# S7G7_footprint_Power_Meter_Only_v1p20.net
KiCad netlist of a schematic drawn in EAGLE
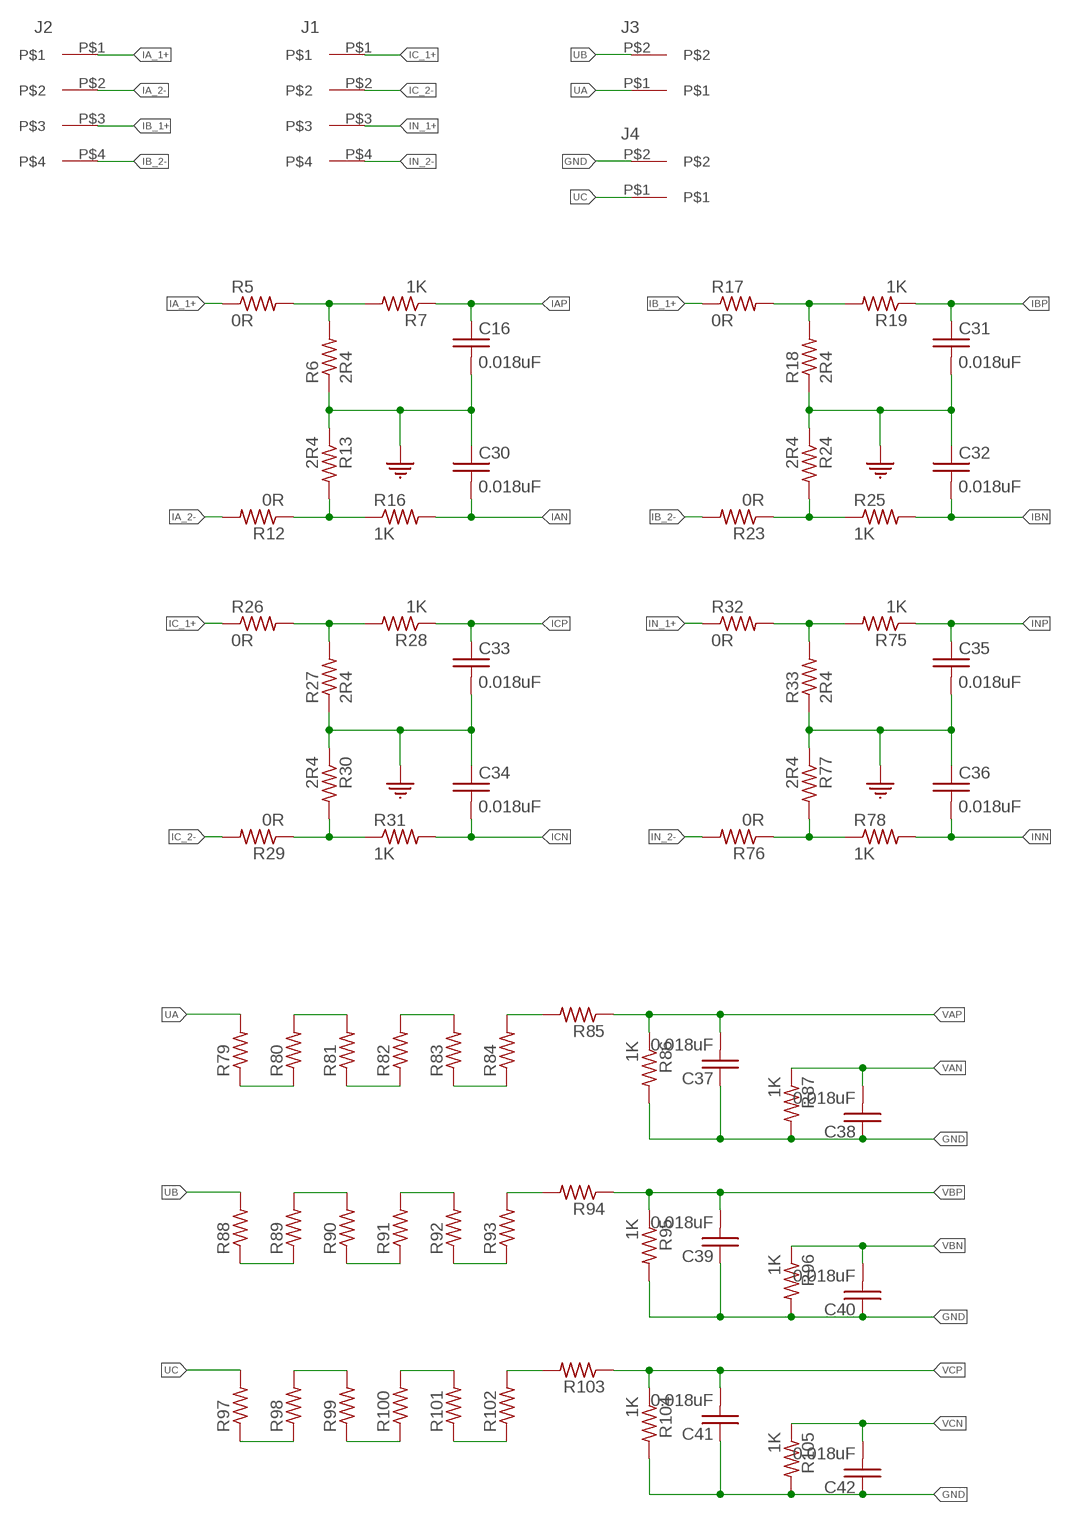
[diagram p0: schematic, sheet 1, part 1 of 2]
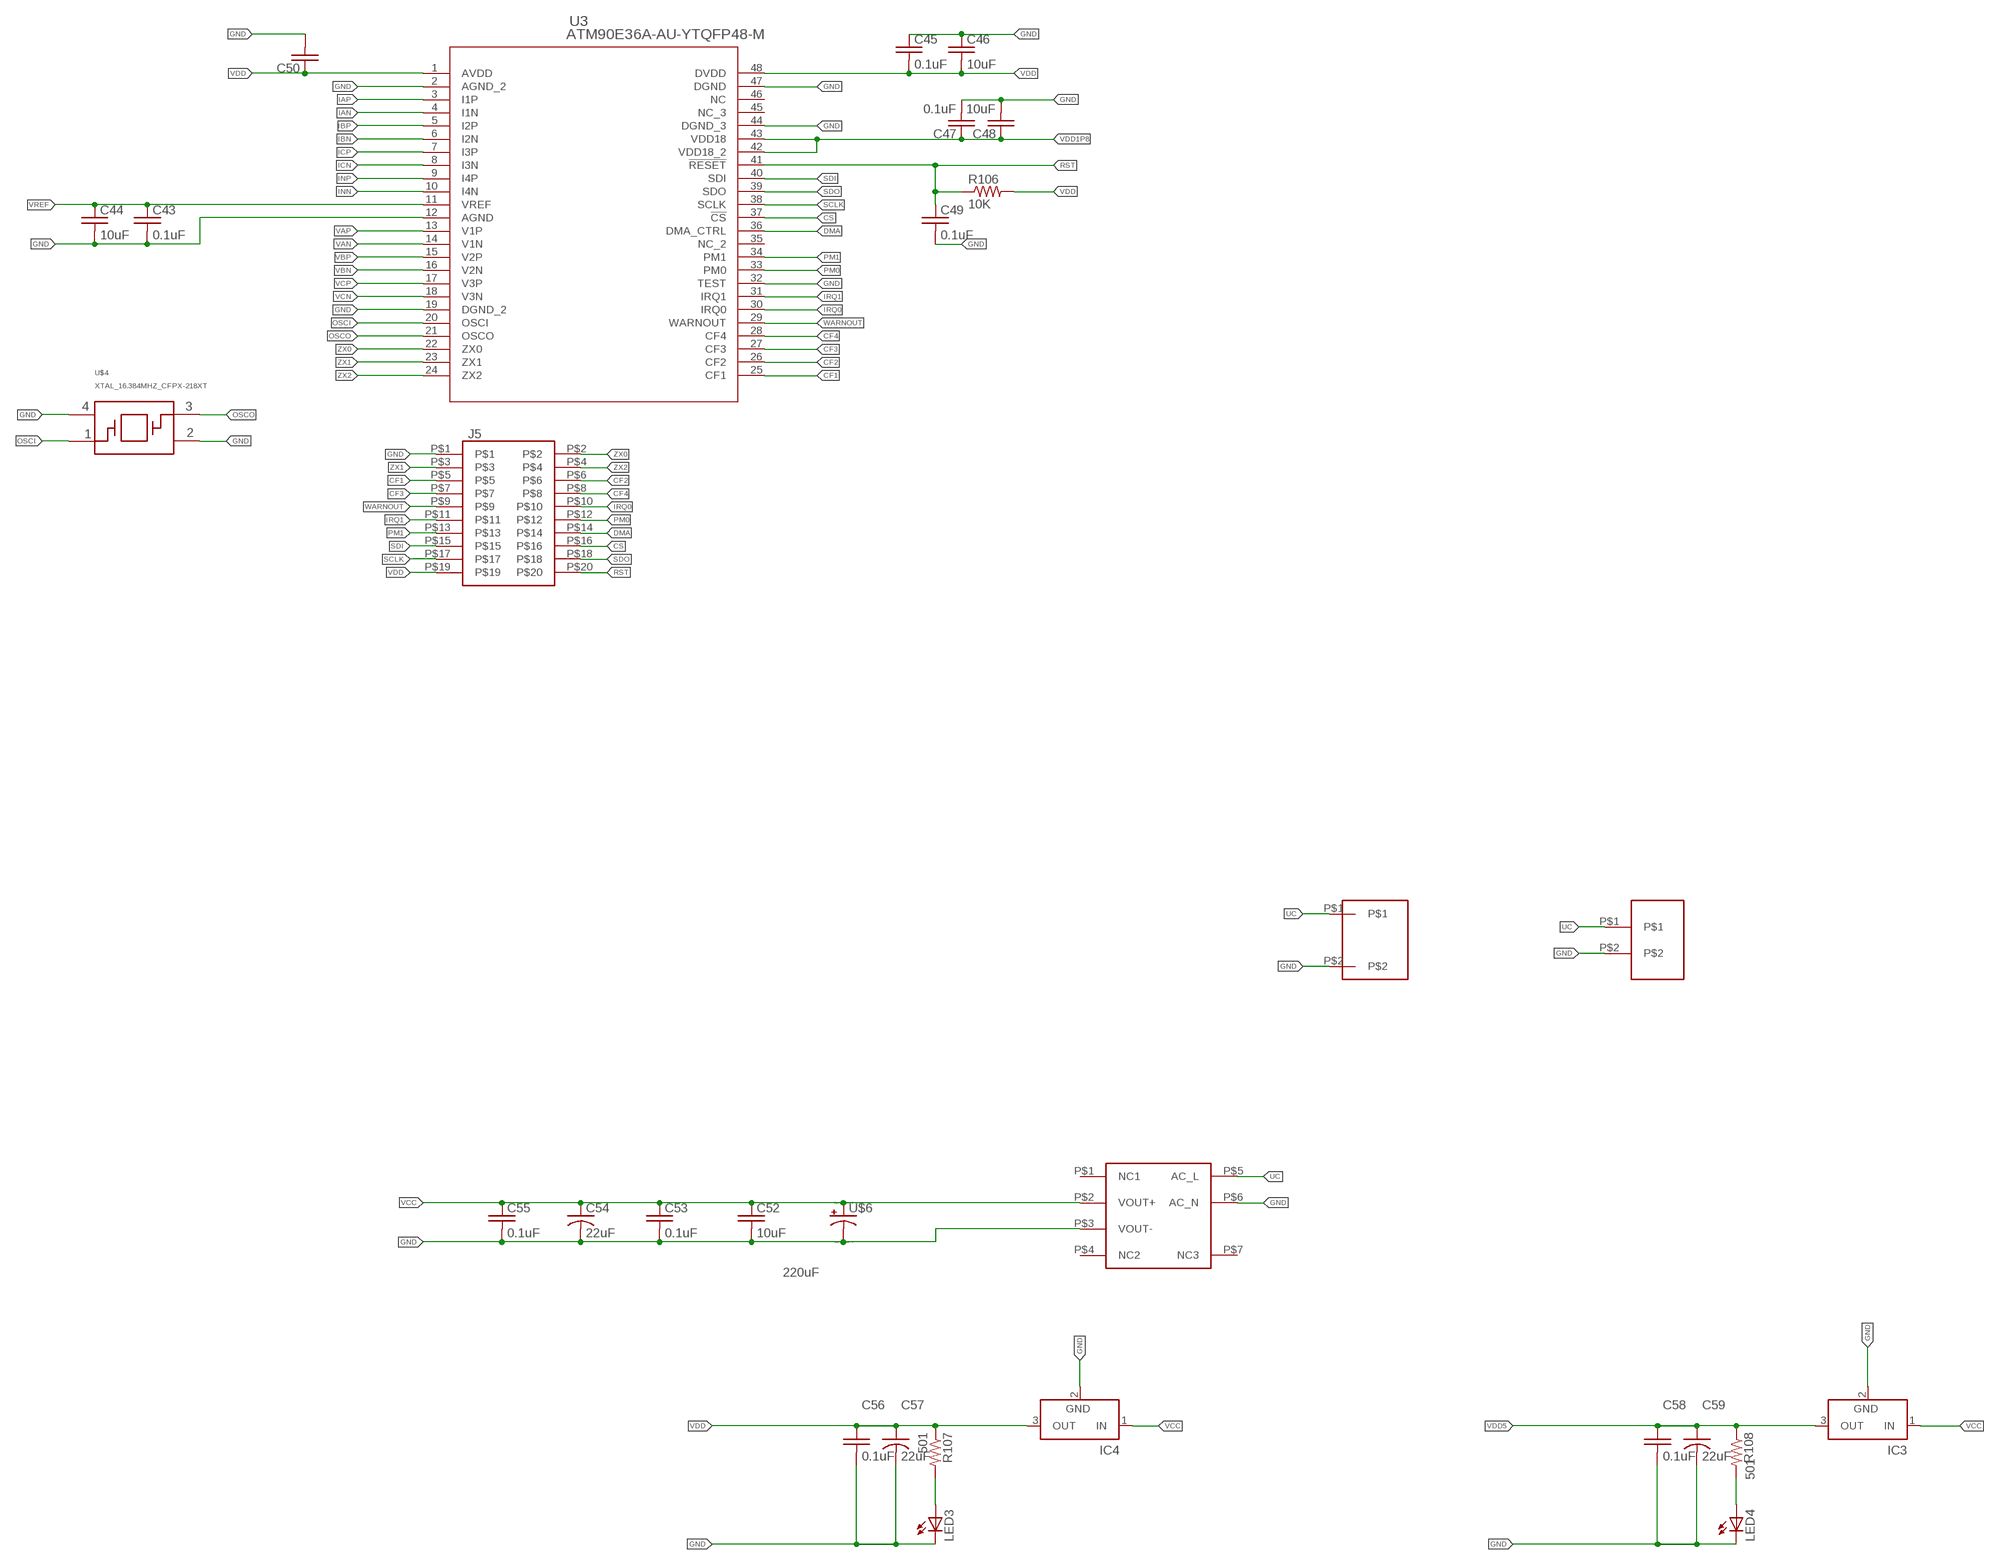
[diagram p1: schematic, sheet 1, part 2 of 2]

(export (version "E")
  (design (tool "Eeschema 10.0.6"))
  (components
    (comp (ref "C16")
      (value "0.018uF")
      (footprint "eagle-import:0402")
      (libsource (lib "eagle-import") (part "C_0402"))
    )
    (comp (ref "C30")
      (value "0.018uF")
      (footprint "eagle-import:0402")
      (libsource (lib "eagle-import") (part "C_0402"))
    )
    (comp (ref "C31")
      (value "0.018uF")
      (footprint "eagle-import:0402")
      (libsource (lib "eagle-import") (part "C_0402"))
    )
    (comp (ref "C32")
      (value "0.018uF")
      (footprint "eagle-import:0402")
      (libsource (lib "eagle-import") (part "C_0402"))
    )
    (comp (ref "C33")
      (value "0.018uF")
      (footprint "eagle-import:0402")
      (libsource (lib "eagle-import") (part "C_0402"))
    )
    (comp (ref "C34")
      (value "0.018uF")
      (footprint "eagle-import:0402")
      (libsource (lib "eagle-import") (part "C_0402"))
    )
    (comp (ref "C35")
      (value "0.018uF")
      (footprint "eagle-import:0402")
      (libsource (lib "eagle-import") (part "C_0402"))
    )
    (comp (ref "C36")
      (value "0.018uF")
      (footprint "eagle-import:0402")
      (libsource (lib "eagle-import") (part "C_0402"))
    )
    (comp (ref "C37")
      (value "0.018uF")
      (footprint "eagle-import:0402")
      (libsource (lib "eagle-import") (part "C_0402"))
    )
    (comp (ref "C38")
      (value "0.018uF")
      (footprint "eagle-import:0402")
      (libsource (lib "eagle-import") (part "C_0402"))
    )
    (comp (ref "C39")
      (value "0.018uF")
      (footprint "eagle-import:0402")
      (libsource (lib "eagle-import") (part "C_0402"))
    )
    (comp (ref "C40")
      (value "0.018uF")
      (footprint "eagle-import:0402")
      (libsource (lib "eagle-import") (part "C_0402"))
    )
    (comp (ref "C41")
      (value "0.018uF")
      (footprint "eagle-import:0402")
      (libsource (lib "eagle-import") (part "C_0402"))
    )
    (comp (ref "C42")
      (value "0.018uF")
      (footprint "eagle-import:0402")
      (libsource (lib "eagle-import") (part "C_0402"))
    )
    (comp (ref "C43")
      (value "0.1uF")
      (footprint "eagle-import:0402")
      (libsource (lib "eagle-import") (part "C_0402"))
    )
    (comp (ref "C44")
      (value "10uF")
      (footprint "eagle-import:0402")
      (libsource (lib "eagle-import") (part "C_0402"))
    )
    (comp (ref "C45")
      (value "0.1uF")
      (footprint "eagle-import:0402")
      (libsource (lib "eagle-import") (part "C_0402"))
    )
    (comp (ref "C46")
      (value "10uF")
      (footprint "eagle-import:0402")
      (libsource (lib "eagle-import") (part "C_0402"))
    )
    (comp (ref "C47")
      (value "0.1uF")
      (footprint "eagle-import:0402")
      (libsource (lib "eagle-import") (part "C_0402"))
    )
    (comp (ref "C48")
      (value "10uF")
      (footprint "eagle-import:0402")
      (libsource (lib "eagle-import") (part "C_0402"))
    )
    (comp (ref "C49")
      (value "0.1uF")
      (footprint "eagle-import:0402")
      (libsource (lib "eagle-import") (part "C_0402"))
    )
    (comp (ref "C50")
      (value "C_0402")
      (footprint "eagle-import:0402")
      (libsource (lib "eagle-import") (part "C_0402"))
    )
    (comp (ref "C51")
      (value "CAP_THIN_FILM_TDK_32922CAP")
      (footprint "eagle-import:CAP_THIN_FILM_32922")
      (libsource (lib "eagle-import") (part "CAP_THIN_FILM_TDK_32922CAP"))
    )
    (comp (ref "C52")
      (value "10uF")
      (footprint "eagle-import:0402")
      (libsource (lib "eagle-import") (part "C_0402"))
    )
    (comp (ref "C53")
      (value "0.1uF")
      (footprint "eagle-import:0402")
      (libsource (lib "eagle-import") (part "C_0402"))
    )
    (comp (ref "C54")
      (value "22uF")
      (footprint "eagle-import:C1206")
      (libsource (lib "eagle-import") (part "C-USC1206"))
    )
    (comp (ref "C55")
      (value "0.1uF")
      (footprint "eagle-import:0402")
      (libsource (lib "eagle-import") (part "C_0402"))
    )
    (comp (ref "C56")
      (value "0.1uF")
      (footprint "eagle-import:0402")
      (libsource (lib "eagle-import") (part "C_0402"))
    )
    (comp (ref "C57")
      (value "22uF")
      (footprint "eagle-import:C1206")
      (libsource (lib "eagle-import") (part "C-USC1206"))
    )
    (comp (ref "C58")
      (value "0.1uF")
      (footprint "eagle-import:0402")
      (libsource (lib "eagle-import") (part "C_0402"))
    )
    (comp (ref "C59")
      (value "22uF")
      (footprint "eagle-import:C1206")
      (libsource (lib "eagle-import") (part "C-USC1206"))
    )
    (comp (ref "IC3")
      (value "LT1129CST5")
      (footprint "eagle-import:SOT223")
      (fields (field (name "MPN") "LT1129CST-5#PBF"))
      (libsource (lib "eagle-import") (part "LT1129CST5"))
    )
    (comp (ref "IC4")
      (value "LT1129CST3")
      (footprint "eagle-import:SOT223")
      (fields (field (name "MPN") "LT1129CST-5#PBF"))
      (libsource (lib "eagle-import") (part "LT1129CST3"))
    )
    (comp (ref "J1")
      (value "3.81MM_1_X_4_RT_ANGLE_PLUG_HEADER")
      (footprint "eagle-import:1X4_3.81MM_PITCH")
      (libsource (lib "eagle-import") (part "3.81MM_1_X_4_RT_ANGLE_PLUG_HEADER"))
    )
    (comp (ref "J2")
      (value "3.81MM_1_X_4_RT_ANGLE_PLUG_HEADER")
      (footprint "eagle-import:1X4_3.81MM_PITCH")
      (libsource (lib "eagle-import") (part "3.81MM_1_X_4_RT_ANGLE_PLUG_HEADER"))
    )
    (comp (ref "J3")
      (value "3.81MM_1_X_2_RT_ANGLE_PLUG_HEADER")
      (footprint "eagle-import:2_3.81MM_PITCH")
      (libsource (lib "eagle-import") (part "3.81MM_1_X_2_RT_ANGLE_PLUG_HEADER"))
    )
    (comp (ref "J4")
      (value "3.81MM_1_X_2_RT_ANGLE_PLUG_HEADER")
      (footprint "eagle-import:2_3.81MM_PITCH")
      (libsource (lib "eagle-import") (part "3.81MM_1_X_2_RT_ANGLE_PLUG_HEADER"))
    )
    (comp (ref "J5")
      (value "2_X_10_HEADER_GENERIC")
      (footprint "eagle-import:2_X_10_.1_INCH")
      (libsource (lib "eagle-import") (part "2_X_10_HEADER_GENERIC"))
    )
    (comp (ref "LED3")
      (value "LED_0805_GREEN")
      (footprint "eagle-import:LED_0805_GREEN")
      (libsource (lib "eagle-import") (part "LED_0805_GREEN"))
    )
    (comp (ref "LED4")
      (value "LED_0805_GREEN")
      (footprint "eagle-import:LED_0805_GREEN")
      (libsource (lib "eagle-import") (part "LED_0805_GREEN"))
    )
    (comp (ref "R5")
      (value "0R")
      (footprint "eagle-import:0402")
      (libsource (lib "eagle-import") (part "R_0402"))
    )
    (comp (ref "R6")
      (value "2R4")
      (footprint "eagle-import:0402")
      (libsource (lib "eagle-import") (part "R_0402"))
    )
    (comp (ref "R7")
      (value "1K")
      (footprint "eagle-import:0402")
      (libsource (lib "eagle-import") (part "R_0402"))
    )
    (comp (ref "R12")
      (value "0R")
      (footprint "eagle-import:0402")
      (libsource (lib "eagle-import") (part "R_0402"))
    )
    (comp (ref "R13")
      (value "2R4")
      (footprint "eagle-import:0402")
      (libsource (lib "eagle-import") (part "R_0402"))
    )
    (comp (ref "R16")
      (value "1K")
      (footprint "eagle-import:0402")
      (libsource (lib "eagle-import") (part "R_0402"))
    )
    (comp (ref "R17")
      (value "0R")
      (footprint "eagle-import:0402")
      (libsource (lib "eagle-import") (part "R_0402"))
    )
    (comp (ref "R18")
      (value "2R4")
      (footprint "eagle-import:0402")
      (libsource (lib "eagle-import") (part "R_0402"))
    )
    (comp (ref "R19")
      (value "1K")
      (footprint "eagle-import:0402")
      (libsource (lib "eagle-import") (part "R_0402"))
    )
    (comp (ref "R23")
      (value "0R")
      (footprint "eagle-import:0402")
      (libsource (lib "eagle-import") (part "R_0402"))
    )
    (comp (ref "R24")
      (value "2R4")
      (footprint "eagle-import:0402")
      (libsource (lib "eagle-import") (part "R_0402"))
    )
    (comp (ref "R25")
      (value "1K")
      (footprint "eagle-import:0402")
      (libsource (lib "eagle-import") (part "R_0402"))
    )
    (comp (ref "R26")
      (value "0R")
      (footprint "eagle-import:0402")
      (libsource (lib "eagle-import") (part "R_0402"))
    )
    (comp (ref "R27")
      (value "2R4")
      (footprint "eagle-import:0402")
      (libsource (lib "eagle-import") (part "R_0402"))
    )
    (comp (ref "R28")
      (value "1K")
      (footprint "eagle-import:0402")
      (libsource (lib "eagle-import") (part "R_0402"))
    )
    (comp (ref "R29")
      (value "0R")
      (footprint "eagle-import:0402")
      (libsource (lib "eagle-import") (part "R_0402"))
    )
    (comp (ref "R30")
      (value "2R4")
      (footprint "eagle-import:0402")
      (libsource (lib "eagle-import") (part "R_0402"))
    )
    (comp (ref "R31")
      (value "1K")
      (footprint "eagle-import:0402")
      (libsource (lib "eagle-import") (part "R_0402"))
    )
    (comp (ref "R32")
      (value "0R")
      (footprint "eagle-import:0402")
      (libsource (lib "eagle-import") (part "R_0402"))
    )
    (comp (ref "R33")
      (value "2R4")
      (footprint "eagle-import:0402")
      (libsource (lib "eagle-import") (part "R_0402"))
    )
    (comp (ref "R75")
      (value "1K")
      (footprint "eagle-import:0402")
      (libsource (lib "eagle-import") (part "R_0402"))
    )
    (comp (ref "R76")
      (value "0R")
      (footprint "eagle-import:0402")
      (libsource (lib "eagle-import") (part "R_0402"))
    )
    (comp (ref "R77")
      (value "2R4")
      (footprint "eagle-import:0402")
      (libsource (lib "eagle-import") (part "R_0402"))
    )
    (comp (ref "R78")
      (value "1K")
      (footprint "eagle-import:0402")
      (libsource (lib "eagle-import") (part "R_0402"))
    )
    (comp (ref "R79")
      (value "R_0402")
      (footprint "eagle-import:0402")
      (libsource (lib "eagle-import") (part "R_0402"))
    )
    (comp (ref "R80")
      (value "R_0402")
      (footprint "eagle-import:0402")
      (libsource (lib "eagle-import") (part "R_0402"))
    )
    (comp (ref "R81")
      (value "R_0402")
      (footprint "eagle-import:0402")
      (libsource (lib "eagle-import") (part "R_0402"))
    )
    (comp (ref "R82")
      (value "R_0402")
      (footprint "eagle-import:0402")
      (libsource (lib "eagle-import") (part "R_0402"))
    )
    (comp (ref "R83")
      (value "R_0402")
      (footprint "eagle-import:0402")
      (libsource (lib "eagle-import") (part "R_0402"))
    )
    (comp (ref "R84")
      (value "R_0402")
      (footprint "eagle-import:0402")
      (libsource (lib "eagle-import") (part "R_0402"))
    )
    (comp (ref "R85")
      (value "R_0402")
      (footprint "eagle-import:0402")
      (libsource (lib "eagle-import") (part "R_0402"))
    )
    (comp (ref "R86")
      (value "1K")
      (footprint "eagle-import:0402")
      (libsource (lib "eagle-import") (part "R_0402"))
    )
    (comp (ref "R87")
      (value "1K")
      (footprint "eagle-import:0402")
      (libsource (lib "eagle-import") (part "R_0402"))
    )
    (comp (ref "R88")
      (value "R_0402")
      (footprint "eagle-import:0402")
      (libsource (lib "eagle-import") (part "R_0402"))
    )
    (comp (ref "R89")
      (value "R_0402")
      (footprint "eagle-import:0402")
      (libsource (lib "eagle-import") (part "R_0402"))
    )
    (comp (ref "R90")
      (value "R_0402")
      (footprint "eagle-import:0402")
      (libsource (lib "eagle-import") (part "R_0402"))
    )
    (comp (ref "R91")
      (value "R_0402")
      (footprint "eagle-import:0402")
      (libsource (lib "eagle-import") (part "R_0402"))
    )
    (comp (ref "R92")
      (value "R_0402")
      (footprint "eagle-import:0402")
      (libsource (lib "eagle-import") (part "R_0402"))
    )
    (comp (ref "R93")
      (value "R_0402")
      (footprint "eagle-import:0402")
      (libsource (lib "eagle-import") (part "R_0402"))
    )
    (comp (ref "R94")
      (value "R_0402")
      (footprint "eagle-import:0402")
      (libsource (lib "eagle-import") (part "R_0402"))
    )
    (comp (ref "R95")
      (value "1K")
      (footprint "eagle-import:0402")
      (libsource (lib "eagle-import") (part "R_0402"))
    )
    (comp (ref "R96")
      (value "1K")
      (footprint "eagle-import:0402")
      (libsource (lib "eagle-import") (part "R_0402"))
    )
    (comp (ref "R97")
      (value "R_0402")
      (footprint "eagle-import:0402")
      (libsource (lib "eagle-import") (part "R_0402"))
    )
    (comp (ref "R98")
      (value "R_0402")
      (footprint "eagle-import:0402")
      (libsource (lib "eagle-import") (part "R_0402"))
    )
    (comp (ref "R99")
      (value "R_0402")
      (footprint "eagle-import:0402")
      (libsource (lib "eagle-import") (part "R_0402"))
    )
    (comp (ref "R100")
      (value "R_0402")
      (footprint "eagle-import:0402")
      (libsource (lib "eagle-import") (part "R_0402"))
    )
    (comp (ref "R101")
      (value "R_0402")
      (footprint "eagle-import:0402")
      (libsource (lib "eagle-import") (part "R_0402"))
    )
    (comp (ref "R102")
      (value "R_0402")
      (footprint "eagle-import:0402")
      (libsource (lib "eagle-import") (part "R_0402"))
    )
    (comp (ref "R103")
      (value "R_0402")
      (footprint "eagle-import:0402")
      (libsource (lib "eagle-import") (part "R_0402"))
    )
    (comp (ref "R104")
      (value "1K")
      (footprint "eagle-import:0402")
      (libsource (lib "eagle-import") (part "R_0402"))
    )
    (comp (ref "R105")
      (value "1K")
      (footprint "eagle-import:0402")
      (libsource (lib "eagle-import") (part "R_0402"))
    )
    (comp (ref "R106")
      (value "10K")
      (footprint "eagle-import:0402")
      (libsource (lib "eagle-import") (part "R_0402"))
    )
    (comp (ref "R107")
      (value "501")
      (footprint "eagle-import:0402")
      (libsource (lib "eagle-import") (part "R_0402"))
    )
    (comp (ref "R108")
      (value "501")
      (footprint "eagle-import:0402")
      (libsource (lib "eagle-import") (part "R_0402"))
    )
    (comp (ref "U$4")
      (value "XTAL_16.384MHZ_CFPX-218XT")
      (footprint "eagle-import:XTAL_2.5X2.0")
      (libsource (lib "eagle-import") (part "XTAL_16.384MHZ_CFPX-218XT"))
    )
    (comp (ref "U$5")
      (value "VAR_10MM_VDRUS10")
      (footprint "eagle-import:VAR_10MM_VDRUS10")
      (libsource (lib "eagle-import") (part "VAR_10MM_VDRUS10"))
    )
    (comp (ref "U$6")
      (value "220uF")
      (footprint "eagle-import:C_AL_ELECTROLYTIC_SMD_220UF")
      (libsource (lib "eagle-import") (part "C_AL_ELECTROLYTIC_SMD_220UF"))
    )
    (comp (ref "U3")
      (value "ATM90E36A-AU-YTQFP48-M")
      (footprint "eagle-import:TQFP48-M")
      (fields (field (name "MANUFACTURER_PART_NUMBER") "ATM90E36AAUY"))
      (libsource (lib "eagle-import") (part "ATM90E36A-AU-YTQFP48-M"))
    )
    (comp (ref "U4")
      (value "TMLM_04109")
      (footprint "eagle-import:TMLM04")
      (libsource (lib "eagle-import") (part "TMLM_04109"))
    )
  )
  (nets
    (net (code "1") (name "CF1") (class "Default")
      (node (ref "J5") (pin "P$5") (pinfunction "P$5_P$5") (pintype "bidirectional"))
      (node (ref "U3") (pin "25") (pinfunction "CF1_25") (pintype "output"))
    )
    (net (code "2") (name "CF2") (class "Default")
      (node (ref "J5") (pin "P$6") (pinfunction "P$6_P$6") (pintype "bidirectional"))
      (node (ref "U3") (pin "26") (pinfunction "CF2_26") (pintype "output"))
    )
    (net (code "3") (name "CF3") (class "Default")
      (node (ref "J5") (pin "P$7") (pinfunction "P$7_P$7") (pintype "bidirectional"))
      (node (ref "U3") (pin "27") (pinfunction "CF3_27") (pintype "output"))
    )
    (net (code "4") (name "CF4") (class "Default")
      (node (ref "J5") (pin "P$8") (pinfunction "P$8_P$8") (pintype "bidirectional"))
      (node (ref "U3") (pin "28") (pinfunction "CF4_28") (pintype "output"))
    )
    (net (code "5") (name "CS") (class "Default")
      (node (ref "J5") (pin "P$16") (pinfunction "P$16_P$16") (pintype "bidirectional"))
      (node (ref "U3") (pin "37") (pinfunction "~{CS}_37") (pintype "bidirectional"))
    )
    (net (code "6") (name "DMA") (class "Default")
      (node (ref "J5") (pin "P$14") (pinfunction "P$14_P$14") (pintype "bidirectional"))
      (node (ref "U3") (pin "36") (pinfunction "DMA_CTRL_36") (pintype "input"))
    )
    (net (code "7") (name "GND") (class "Default")
      (node (ref "C16") (pin "P$2") (pinfunction "2_P$2") (pintype "passive"))
      (node (ref "C30") (pin "P$1") (pinfunction "1_P$1") (pintype "passive"))
      (node (ref "C31") (pin "P$2") (pinfunction "2_P$2") (pintype "passive"))
      (node (ref "C32") (pin "P$1") (pinfunction "1_P$1") (pintype "passive"))
      (node (ref "C33") (pin "P$2") (pinfunction "2_P$2") (pintype "passive"))
      (node (ref "C34") (pin "P$1") (pinfunction "1_P$1") (pintype "passive"))
      (node (ref "C35") (pin "P$2") (pinfunction "2_P$2") (pintype "passive"))
      (node (ref "C36") (pin "P$1") (pinfunction "1_P$1") (pintype "passive"))
      (node (ref "C37") (pin "P$1") (pinfunction "1_P$1") (pintype "passive"))
      (node (ref "C38") (pin "P$1") (pinfunction "1_P$1") (pintype "passive"))
      (node (ref "C39") (pin "P$1") (pinfunction "1_P$1") (pintype "passive"))
      (node (ref "C40") (pin "P$1") (pinfunction "1_P$1") (pintype "passive"))
      (node (ref "C41") (pin "P$1") (pinfunction "1_P$1") (pintype "passive"))
      (node (ref "C42") (pin "P$1") (pinfunction "1_P$1") (pintype "passive"))
      (node (ref "C43") (pin "P$2") (pinfunction "2_P$2") (pintype "passive"))
      (node (ref "C44") (pin "P$2") (pinfunction "2_P$2") (pintype "passive"))
      (node (ref "C45") (pin "P$1") (pinfunction "1_P$1") (pintype "passive"))
      (node (ref "C46") (pin "P$1") (pinfunction "1_P$1") (pintype "passive"))
      (node (ref "C47") (pin "P$2") (pinfunction "2_P$2") (pintype "passive"))
      (node (ref "C48") (pin "P$2") (pinfunction "2_P$2") (pintype "passive"))
      (node (ref "C49") (pin "P$2") (pinfunction "2_P$2") (pintype "passive"))
      (node (ref "C50") (pin "P$2") (pinfunction "2_P$2") (pintype "passive"))
      (node (ref "C51") (pin "P$2") (pinfunction "P$2_P$2") (pintype "bidirectional"))
      (node (ref "C52") (pin "P$2") (pinfunction "2_P$2") (pintype "passive"))
      (node (ref "C53") (pin "P$2") (pinfunction "2_P$2") (pintype "passive"))
      (node (ref "C54") (pin "2") (pinfunction "2_2") (pintype "passive"))
      (node (ref "C55") (pin "P$2") (pinfunction "2_P$2") (pintype "passive"))
      (node (ref "C56") (pin "P$2") (pinfunction "2_P$2") (pintype "passive"))
      (node (ref "C57") (pin "2") (pinfunction "2_2") (pintype "passive"))
      (node (ref "C58") (pin "P$2") (pinfunction "2_P$2") (pintype "passive"))
      (node (ref "C59") (pin "2") (pinfunction "2_2") (pintype "passive"))
      (node (ref "IC3") (pin "2") (pinfunction "GND_2") (pintype "power_in"))
      (node (ref "IC4") (pin "2") (pinfunction "GND_2") (pintype "power_in"))
      (node (ref "J4") (pin "P$2") (pinfunction "P$2_P$2") (pintype "bidirectional"))
      (node (ref "J5") (pin "P$1") (pinfunction "P$1_P$1") (pintype "bidirectional"))
      (node (ref "LED3") (pin "C") (pinfunction "C_C") (pintype "passive"))
      (node (ref "LED4") (pin "C") (pinfunction "C_C") (pintype "passive"))
      (node (ref "R104") (pin "P$2") (pinfunction "2_P$2") (pintype "passive"))
      (node (ref "R105") (pin "P$2") (pinfunction "2_P$2") (pintype "passive"))
      (node (ref "R13") (pin "P$1") (pinfunction "1_P$1") (pintype "passive"))
      (node (ref "R18") (pin "P$1") (pinfunction "1_P$1") (pintype "passive"))
      (node (ref "R24") (pin "P$1") (pinfunction "1_P$1") (pintype "passive"))
      (node (ref "R27") (pin "P$1") (pinfunction "1_P$1") (pintype "passive"))
      (node (ref "R30") (pin "P$1") (pinfunction "1_P$1") (pintype "passive"))
      (node (ref "R33") (pin "P$1") (pinfunction "1_P$1") (pintype "passive"))
      (node (ref "R6") (pin "P$1") (pinfunction "1_P$1") (pintype "passive"))
      (node (ref "R77") (pin "P$1") (pinfunction "1_P$1") (pintype "passive"))
      (node (ref "R86") (pin "P$2") (pinfunction "2_P$2") (pintype "passive"))
      (node (ref "R87") (pin "P$2") (pinfunction "2_P$2") (pintype "passive"))
      (node (ref "R95") (pin "P$2") (pinfunction "2_P$2") (pintype "passive"))
      (node (ref "R96") (pin "P$2") (pinfunction "2_P$2") (pintype "passive"))
      (node (ref "U$4") (pin "2") (pinfunction "2_2") (pintype "bidirectional"))
      (node (ref "U$4") (pin "4") (pinfunction "4_4") (pintype "bidirectional"))
      (node (ref "U$5") (pin "P$2") (pinfunction "P$2_P$2") (pintype "bidirectional"))
      (node (ref "U$6") (pin "N-") (pinfunction "-_N-") (pintype "passive"))
      (node (ref "U3") (pin "12") (pinfunction "AGND_12") (pintype "power_in"))
      (node (ref "U3") (pin "19") (pinfunction "DGND_2_19") (pintype "power_in"))
      (node (ref "U3") (pin "2") (pinfunction "AGND_2_2") (pintype "power_in"))
      (node (ref "U3") (pin "32") (pinfunction "TEST_32") (pintype "input"))
      (node (ref "U3") (pin "44") (pinfunction "DGND_3_44") (pintype "power_in"))
      (node (ref "U3") (pin "47") (pinfunction "DGND_47") (pintype "power_in"))
      (node (ref "U4") (pin "P$3") (pinfunction "VOUT-_P$3") (pintype "bidirectional"))
      (node (ref "U4") (pin "P$6") (pinfunction "AC_N_P$6") (pintype "bidirectional"))
    )
    (net (code "8") (name "IAN") (class "Default")
      (node (ref "C30") (pin "P$2") (pinfunction "2_P$2") (pintype "passive"))
      (node (ref "R16") (pin "P$2") (pinfunction "2_P$2") (pintype "passive"))
      (node (ref "U3") (pin "4") (pinfunction "I1N_4") (pintype "input"))
    )
    (net (code "9") (name "IAP") (class "Default")
      (node (ref "C16") (pin "P$1") (pinfunction "1_P$1") (pintype "passive"))
      (node (ref "R7") (pin "P$1") (pinfunction "1_P$1") (pintype "passive"))
      (node (ref "U3") (pin "3") (pinfunction "I1P_3") (pintype "input"))
    )
    (net (code "10") (name "IA_1+") (class "Default")
      (node (ref "J2") (pin "P$1") (pinfunction "P$1_P$1") (pintype "bidirectional"))
      (node (ref "R5") (pin "P$1") (pinfunction "1_P$1") (pintype "passive"))
    )
    (net (code "11") (name "IA_2-") (class "Default")
      (node (ref "J2") (pin "P$2") (pinfunction "P$2_P$2") (pintype "bidirectional"))
      (node (ref "R12") (pin "P$2") (pinfunction "2_P$2") (pintype "passive"))
    )
    (net (code "12") (name "IBN") (class "Default")
      (node (ref "C32") (pin "P$2") (pinfunction "2_P$2") (pintype "passive"))
      (node (ref "R25") (pin "P$2") (pinfunction "2_P$2") (pintype "passive"))
      (node (ref "U3") (pin "6") (pinfunction "I2N_6") (pintype "input"))
    )
    (net (code "13") (name "IBP") (class "Default")
      (node (ref "C31") (pin "P$1") (pinfunction "1_P$1") (pintype "passive"))
      (node (ref "R19") (pin "P$1") (pinfunction "1_P$1") (pintype "passive"))
      (node (ref "U3") (pin "5") (pinfunction "I2P_5") (pintype "input"))
    )
    (net (code "14") (name "IB_1+") (class "Default")
      (node (ref "J2") (pin "P$3") (pinfunction "P$3_P$3") (pintype "bidirectional"))
      (node (ref "R17") (pin "P$1") (pinfunction "1_P$1") (pintype "passive"))
    )
    (net (code "15") (name "IB_2-") (class "Default")
      (node (ref "J2") (pin "P$4") (pinfunction "P$4_P$4") (pintype "bidirectional"))
      (node (ref "R23") (pin "P$2") (pinfunction "2_P$2") (pintype "passive"))
    )
    (net (code "16") (name "ICN") (class "Default")
      (node (ref "C34") (pin "P$2") (pinfunction "2_P$2") (pintype "passive"))
      (node (ref "R31") (pin "P$2") (pinfunction "2_P$2") (pintype "passive"))
      (node (ref "U3") (pin "8") (pinfunction "I3N_8") (pintype "input"))
    )
    (net (code "17") (name "ICP") (class "Default")
      (node (ref "C33") (pin "P$1") (pinfunction "1_P$1") (pintype "passive"))
      (node (ref "R28") (pin "P$1") (pinfunction "1_P$1") (pintype "passive"))
      (node (ref "U3") (pin "7") (pinfunction "I3P_7") (pintype "input"))
    )
    (net (code "18") (name "IC_1+") (class "Default")
      (node (ref "J1") (pin "P$1") (pinfunction "P$1_P$1") (pintype "bidirectional"))
      (node (ref "R26") (pin "P$1") (pinfunction "1_P$1") (pintype "passive"))
    )
    (net (code "19") (name "IC_2-") (class "Default")
      (node (ref "J1") (pin "P$2") (pinfunction "P$2_P$2") (pintype "bidirectional"))
      (node (ref "R29") (pin "P$2") (pinfunction "2_P$2") (pintype "passive"))
    )
    (net (code "20") (name "INN") (class "Default")
      (node (ref "C36") (pin "P$2") (pinfunction "2_P$2") (pintype "passive"))
      (node (ref "R78") (pin "P$2") (pinfunction "2_P$2") (pintype "passive"))
      (node (ref "U3") (pin "10") (pinfunction "I4N_10") (pintype "input"))
    )
    (net (code "21") (name "INP") (class "Default")
      (node (ref "C35") (pin "P$1") (pinfunction "1_P$1") (pintype "passive"))
      (node (ref "R75") (pin "P$1") (pinfunction "1_P$1") (pintype "passive"))
      (node (ref "U3") (pin "9") (pinfunction "I4P_9") (pintype "input"))
    )
    (net (code "22") (name "IN_1+") (class "Default")
      (node (ref "J1") (pin "P$3") (pinfunction "P$3_P$3") (pintype "bidirectional"))
      (node (ref "R32") (pin "P$1") (pinfunction "1_P$1") (pintype "passive"))
    )
    (net (code "23") (name "IN_2-") (class "Default")
      (node (ref "J1") (pin "P$4") (pinfunction "P$4_P$4") (pintype "bidirectional"))
      (node (ref "R76") (pin "P$2") (pinfunction "2_P$2") (pintype "passive"))
    )
    (net (code "24") (name "IRQ0") (class "Default")
      (node (ref "J5") (pin "P$10") (pinfunction "P$10_P$10") (pintype "bidirectional"))
      (node (ref "U3") (pin "30") (pinfunction "IRQ0_30") (pintype "output"))
    )
    (net (code "25") (name "IRQ1") (class "Default")
      (node (ref "J5") (pin "P$11") (pinfunction "P$11_P$11") (pintype "bidirectional"))
      (node (ref "U3") (pin "31") (pinfunction "IRQ1_31") (pintype "output"))
    )
    (net (code "26") (name "Net-(R5-2)") (class "Default")
      (node (ref "R5") (pin "P$2") (pinfunction "2_P$2") (pintype "passive"))
      (node (ref "R6") (pin "P$2") (pinfunction "2_P$2") (pintype "passive"))
      (node (ref "R7") (pin "P$2") (pinfunction "2_P$2") (pintype "passive"))
    )
    (net (code "27") (name "Net-(R12-1)") (class "Default")
      (node (ref "R12") (pin "P$1") (pinfunction "1_P$1") (pintype "passive"))
      (node (ref "R13") (pin "P$2") (pinfunction "2_P$2") (pintype "passive"))
      (node (ref "R16") (pin "P$1") (pinfunction "1_P$1") (pintype "passive"))
    )
    (net (code "28") (name "Net-(R17-2)") (class "Default")
      (node (ref "R17") (pin "P$2") (pinfunction "2_P$2") (pintype "passive"))
      (node (ref "R18") (pin "P$2") (pinfunction "2_P$2") (pintype "passive"))
      (node (ref "R19") (pin "P$2") (pinfunction "2_P$2") (pintype "passive"))
    )
    (net (code "29") (name "Net-(R23-1)") (class "Default")
      (node (ref "R23") (pin "P$1") (pinfunction "1_P$1") (pintype "passive"))
      (node (ref "R24") (pin "P$2") (pinfunction "2_P$2") (pintype "passive"))
      (node (ref "R25") (pin "P$1") (pinfunction "1_P$1") (pintype "passive"))
    )
    (net (code "30") (name "Net-(R26-2)") (class "Default")
      (node (ref "R26") (pin "P$2") (pinfunction "2_P$2") (pintype "passive"))
      (node (ref "R27") (pin "P$2") (pinfunction "2_P$2") (pintype "passive"))
      (node (ref "R28") (pin "P$2") (pinfunction "2_P$2") (pintype "passive"))
    )
    (net (code "31") (name "Net-(R29-1)") (class "Default")
      (node (ref "R29") (pin "P$1") (pinfunction "1_P$1") (pintype "passive"))
      (node (ref "R30") (pin "P$2") (pinfunction "2_P$2") (pintype "passive"))
      (node (ref "R31") (pin "P$1") (pinfunction "1_P$1") (pintype "passive"))
    )
    (net (code "32") (name "Net-(R32-2)") (class "Default")
      (node (ref "R32") (pin "P$2") (pinfunction "2_P$2") (pintype "passive"))
      (node (ref "R33") (pin "P$2") (pinfunction "2_P$2") (pintype "passive"))
      (node (ref "R75") (pin "P$2") (pinfunction "2_P$2") (pintype "passive"))
    )
    (net (code "33") (name "Net-(R76-1)") (class "Default")
      (node (ref "R76") (pin "P$1") (pinfunction "1_P$1") (pintype "passive"))
      (node (ref "R77") (pin "P$2") (pinfunction "2_P$2") (pintype "passive"))
      (node (ref "R78") (pin "P$1") (pinfunction "1_P$1") (pintype "passive"))
    )
    (net (code "34") (name "Net-(R79-1)") (class "Default")
      (node (ref "R79") (pin "P$1") (pinfunction "1_P$1") (pintype "passive"))
      (node (ref "R80") (pin "P$1") (pinfunction "1_P$1") (pintype "passive"))
    )
    (net (code "35") (name "Net-(R80-2)") (class "Default")
      (node (ref "R80") (pin "P$2") (pinfunction "2_P$2") (pintype "passive"))
      (node (ref "R81") (pin "P$2") (pinfunction "2_P$2") (pintype "passive"))
    )
    (net (code "36") (name "Net-(R81-1)") (class "Default")
      (node (ref "R81") (pin "P$1") (pinfunction "1_P$1") (pintype "passive"))
      (node (ref "R82") (pin "P$1") (pinfunction "1_P$1") (pintype "passive"))
    )
    (net (code "37") (name "Net-(R82-2)") (class "Default")
      (node (ref "R82") (pin "P$2") (pinfunction "2_P$2") (pintype "passive"))
      (node (ref "R83") (pin "P$2") (pinfunction "2_P$2") (pintype "passive"))
    )
    (net (code "38") (name "Net-(R83-1)") (class "Default")
      (node (ref "R83") (pin "P$1") (pinfunction "1_P$1") (pintype "passive"))
      (node (ref "R84") (pin "P$1") (pinfunction "1_P$1") (pintype "passive"))
    )
    (net (code "39") (name "Net-(R84-2)") (class "Default")
      (node (ref "R84") (pin "P$2") (pinfunction "2_P$2") (pintype "passive"))
      (node (ref "R85") (pin "P$2") (pinfunction "2_P$2") (pintype "passive"))
    )
    (net (code "40") (name "Net-(R88-1)") (class "Default")
      (node (ref "R88") (pin "P$1") (pinfunction "1_P$1") (pintype "passive"))
      (node (ref "R89") (pin "P$1") (pinfunction "1_P$1") (pintype "passive"))
    )
    (net (code "41") (name "Net-(R89-2)") (class "Default")
      (node (ref "R89") (pin "P$2") (pinfunction "2_P$2") (pintype "passive"))
      (node (ref "R90") (pin "P$2") (pinfunction "2_P$2") (pintype "passive"))
    )
    (net (code "42") (name "Net-(R90-1)") (class "Default")
      (node (ref "R90") (pin "P$1") (pinfunction "1_P$1") (pintype "passive"))
      (node (ref "R91") (pin "P$1") (pinfunction "1_P$1") (pintype "passive"))
    )
    (net (code "43") (name "Net-(R91-2)") (class "Default")
      (node (ref "R91") (pin "P$2") (pinfunction "2_P$2") (pintype "passive"))
      (node (ref "R92") (pin "P$2") (pinfunction "2_P$2") (pintype "passive"))
    )
    (net (code "44") (name "Net-(R92-1)") (class "Default")
      (node (ref "R92") (pin "P$1") (pinfunction "1_P$1") (pintype "passive"))
      (node (ref "R93") (pin "P$1") (pinfunction "1_P$1") (pintype "passive"))
    )
    (net (code "45") (name "Net-(R93-2)") (class "Default")
      (node (ref "R93") (pin "P$2") (pinfunction "2_P$2") (pintype "passive"))
      (node (ref "R94") (pin "P$2") (pinfunction "2_P$2") (pintype "passive"))
    )
    (net (code "46") (name "Net-(R97-1)") (class "Default")
      (node (ref "R97") (pin "P$1") (pinfunction "1_P$1") (pintype "passive"))
      (node (ref "R98") (pin "P$1") (pinfunction "1_P$1") (pintype "passive"))
    )
    (net (code "47") (name "Net-(R98-2)") (class "Default")
      (node (ref "R98") (pin "P$2") (pinfunction "2_P$2") (pintype "passive"))
      (node (ref "R99") (pin "P$2") (pinfunction "2_P$2") (pintype "passive"))
    )
    (net (code "48") (name "Net-(R100-1)") (class "Default")
      (node (ref "R100") (pin "P$1") (pinfunction "1_P$1") (pintype "passive"))
      (node (ref "R99") (pin "P$1") (pinfunction "1_P$1") (pintype "passive"))
    )
    (net (code "49") (name "Net-(R100-2)") (class "Default")
      (node (ref "R100") (pin "P$2") (pinfunction "2_P$2") (pintype "passive"))
      (node (ref "R101") (pin "P$2") (pinfunction "2_P$2") (pintype "passive"))
    )
    (net (code "50") (name "Net-(R101-1)") (class "Default")
      (node (ref "R101") (pin "P$1") (pinfunction "1_P$1") (pintype "passive"))
      (node (ref "R102") (pin "P$1") (pinfunction "1_P$1") (pintype "passive"))
    )
    (net (code "51") (name "Net-(R102-2)") (class "Default")
      (node (ref "R102") (pin "P$2") (pinfunction "2_P$2") (pintype "passive"))
      (node (ref "R103") (pin "P$2") (pinfunction "2_P$2") (pintype "passive"))
    )
    (net (code "52") (name "Net-(R107-2)") (class "Default")
      (node (ref "LED3") (pin "A") (pinfunction "A_A") (pintype "passive"))
      (node (ref "R107") (pin "P$2") (pinfunction "2_P$2") (pintype "passive"))
    )
    (net (code "53") (name "Net-(R108-2)") (class "Default")
      (node (ref "LED4") (pin "A") (pinfunction "A_A") (pintype "passive"))
      (node (ref "R108") (pin "P$2") (pinfunction "2_P$2") (pintype "passive"))
    )
    (net (code "54") (name "OSCI") (class "Default")
      (node (ref "U$4") (pin "1") (pinfunction "1_1") (pintype "bidirectional"))
      (node (ref "U3") (pin "20") (pinfunction "OSCI_20") (pintype "input"))
    )
    (net (code "55") (name "OSCO") (class "Default")
      (node (ref "U$4") (pin "3") (pinfunction "3_3") (pintype "bidirectional"))
      (node (ref "U3") (pin "21") (pinfunction "OSCO_21") (pintype "output"))
    )
    (net (code "56") (name "PM0") (class "Default")
      (node (ref "J5") (pin "P$12") (pinfunction "P$12_P$12") (pintype "bidirectional"))
      (node (ref "U3") (pin "33") (pinfunction "PM0_33") (pintype "input"))
    )
    (net (code "57") (name "PM1") (class "Default")
      (node (ref "J5") (pin "P$13") (pinfunction "P$13_P$13") (pintype "bidirectional"))
      (node (ref "U3") (pin "34") (pinfunction "PM1_34") (pintype "input"))
    )
    (net (code "58") (name "RST") (class "Default")
      (node (ref "C49") (pin "P$1") (pinfunction "1_P$1") (pintype "passive"))
      (node (ref "J5") (pin "P$20") (pinfunction "P$20_P$20") (pintype "bidirectional"))
      (node (ref "R106") (pin "P$1") (pinfunction "1_P$1") (pintype "passive"))
      (node (ref "U3") (pin "41") (pinfunction "~{RESET}_41") (pintype "input"))
    )
    (net (code "59") (name "SCLK") (class "Default")
      (node (ref "J5") (pin "P$17") (pinfunction "P$17_P$17") (pintype "bidirectional"))
      (node (ref "U3") (pin "38") (pinfunction "SCLK_38") (pintype "bidirectional"))
    )
    (net (code "60") (name "SDI") (class "Default")
      (node (ref "J5") (pin "P$15") (pinfunction "P$15_P$15") (pintype "bidirectional"))
      (node (ref "U3") (pin "40") (pinfunction "SDI_40") (pintype "bidirectional"))
    )
    (net (code "61") (name "SDO") (class "Default")
      (node (ref "J5") (pin "P$18") (pinfunction "P$18_P$18") (pintype "bidirectional"))
      (node (ref "U3") (pin "39") (pinfunction "SDO_39") (pintype "bidirectional"))
    )
    (net (code "62") (name "UA") (class "Default")
      (node (ref "J3") (pin "P$1") (pinfunction "P$1_P$1") (pintype "bidirectional"))
      (node (ref "R79") (pin "P$2") (pinfunction "2_P$2") (pintype "passive"))
    )
    (net (code "63") (name "UB") (class "Default")
      (node (ref "J3") (pin "P$2") (pinfunction "P$2_P$2") (pintype "bidirectional"))
      (node (ref "R88") (pin "P$2") (pinfunction "2_P$2") (pintype "passive"))
    )
    (net (code "64") (name "UC") (class "Default")
      (node (ref "C51") (pin "P$1") (pinfunction "P$1_P$1") (pintype "bidirectional"))
      (node (ref "J4") (pin "P$1") (pinfunction "P$1_P$1") (pintype "bidirectional"))
      (node (ref "R97") (pin "P$2") (pinfunction "2_P$2") (pintype "passive"))
      (node (ref "U$5") (pin "P$1") (pinfunction "P$1_P$1") (pintype "bidirectional"))
      (node (ref "U4") (pin "P$5") (pinfunction "AC_L_P$5") (pintype "bidirectional"))
    )
    (net (code "65") (name "VAN") (class "Default")
      (node (ref "C38") (pin "P$2") (pinfunction "2_P$2") (pintype "passive"))
      (node (ref "R87") (pin "P$1") (pinfunction "1_P$1") (pintype "passive"))
      (node (ref "U3") (pin "14") (pinfunction "V1N_14") (pintype "input"))
    )
    (net (code "66") (name "VAP") (class "Default")
      (node (ref "C37") (pin "P$2") (pinfunction "2_P$2") (pintype "passive"))
      (node (ref "R85") (pin "P$1") (pinfunction "1_P$1") (pintype "passive"))
      (node (ref "R86") (pin "P$1") (pinfunction "1_P$1") (pintype "passive"))
      (node (ref "U3") (pin "13") (pinfunction "V1P_13") (pintype "input"))
    )
    (net (code "67") (name "VBN") (class "Default")
      (node (ref "C40") (pin "P$2") (pinfunction "2_P$2") (pintype "passive"))
      (node (ref "R96") (pin "P$1") (pinfunction "1_P$1") (pintype "passive"))
      (node (ref "U3") (pin "16") (pinfunction "V2N_16") (pintype "input"))
    )
    (net (code "68") (name "VBP") (class "Default")
      (node (ref "C39") (pin "P$2") (pinfunction "2_P$2") (pintype "passive"))
      (node (ref "R94") (pin "P$1") (pinfunction "1_P$1") (pintype "passive"))
      (node (ref "R95") (pin "P$1") (pinfunction "1_P$1") (pintype "passive"))
      (node (ref "U3") (pin "15") (pinfunction "V2P_15") (pintype "input"))
    )
    (net (code "69") (name "VCC") (class "Default")
      (node (ref "C52") (pin "P$1") (pinfunction "1_P$1") (pintype "passive"))
      (node (ref "C53") (pin "P$1") (pinfunction "1_P$1") (pintype "passive"))
      (node (ref "C54") (pin "1") (pinfunction "1_1") (pintype "passive"))
      (node (ref "C55") (pin "P$1") (pinfunction "1_P$1") (pintype "passive"))
      (node (ref "IC3") (pin "1") (pinfunction "IN_1") (pintype "input"))
      (node (ref "IC4") (pin "1") (pinfunction "IN_1") (pintype "input"))
      (node (ref "U$6") (pin "P+") (pinfunction "+_P+") (pintype "passive"))
      (node (ref "U4") (pin "P$2") (pinfunction "VOUT+_P$2") (pintype "bidirectional"))
    )
    (net (code "70") (name "VCN") (class "Default")
      (node (ref "C42") (pin "P$2") (pinfunction "2_P$2") (pintype "passive"))
      (node (ref "R105") (pin "P$1") (pinfunction "1_P$1") (pintype "passive"))
      (node (ref "U3") (pin "18") (pinfunction "V3N_18") (pintype "input"))
    )
    (net (code "71") (name "VCP") (class "Default")
      (node (ref "C41") (pin "P$2") (pinfunction "2_P$2") (pintype "passive"))
      (node (ref "R103") (pin "P$1") (pinfunction "1_P$1") (pintype "passive"))
      (node (ref "R104") (pin "P$1") (pinfunction "1_P$1") (pintype "passive"))
      (node (ref "U3") (pin "17") (pinfunction "V3P_17") (pintype "input"))
    )
    (net (code "72") (name "VDD") (class "Default")
      (node (ref "C45") (pin "P$2") (pinfunction "2_P$2") (pintype "passive"))
      (node (ref "C46") (pin "P$2") (pinfunction "2_P$2") (pintype "passive"))
      (node (ref "C50") (pin "P$1") (pinfunction "1_P$1") (pintype "passive"))
      (node (ref "C56") (pin "P$1") (pinfunction "1_P$1") (pintype "passive"))
      (node (ref "C57") (pin "1") (pinfunction "1_1") (pintype "passive"))
      (node (ref "IC4") (pin "3") (pinfunction "OUT_3") (pintype "output"))
      (node (ref "J5") (pin "P$19") (pinfunction "P$19_P$19") (pintype "bidirectional"))
      (node (ref "R106") (pin "P$2") (pinfunction "2_P$2") (pintype "passive"))
      (node (ref "R107") (pin "P$1") (pinfunction "1_P$1") (pintype "passive"))
      (node (ref "U3") (pin "1") (pinfunction "AVDD_1") (pintype "power_in"))
      (node (ref "U3") (pin "48") (pinfunction "DVDD_48") (pintype "power_in"))
    )
    (net (code "73") (name "VDD1P8") (class "Default")
      (node (ref "C47") (pin "P$1") (pinfunction "1_P$1") (pintype "passive"))
      (node (ref "C48") (pin "P$1") (pinfunction "1_P$1") (pintype "passive"))
      (node (ref "U3") (pin "42") (pinfunction "VDD18_2_42") (pintype "power_in"))
      (node (ref "U3") (pin "43") (pinfunction "VDD18_43") (pintype "power_in"))
    )
    (net (code "74") (name "VDD5") (class "Default")
      (node (ref "C58") (pin "P$1") (pinfunction "1_P$1") (pintype "passive"))
      (node (ref "C59") (pin "1") (pinfunction "1_1") (pintype "passive"))
      (node (ref "IC3") (pin "3") (pinfunction "OUT_3") (pintype "output"))
      (node (ref "R108") (pin "P$1") (pinfunction "1_P$1") (pintype "passive"))
    )
    (net (code "75") (name "VREF") (class "Default")
      (node (ref "C43") (pin "P$1") (pinfunction "1_P$1") (pintype "passive"))
      (node (ref "C44") (pin "P$1") (pinfunction "1_P$1") (pintype "passive"))
      (node (ref "U3") (pin "11") (pinfunction "VREF_11") (pintype "output"))
    )
    (net (code "76") (name "WARNOUT") (class "Default")
      (node (ref "J5") (pin "P$9") (pinfunction "P$9_P$9") (pintype "bidirectional"))
      (node (ref "U3") (pin "29") (pinfunction "WARNOUT_29") (pintype "output"))
    )
    (net (code "77") (name "ZX0") (class "Default")
      (node (ref "J5") (pin "P$2") (pinfunction "P$2_P$2") (pintype "bidirectional"))
      (node (ref "U3") (pin "22") (pinfunction "ZX0_22") (pintype "output"))
    )
    (net (code "78") (name "ZX1") (class "Default")
      (node (ref "J5") (pin "P$3") (pinfunction "P$3_P$3") (pintype "bidirectional"))
      (node (ref "U3") (pin "23") (pinfunction "ZX1_23") (pintype "output"))
    )
    (net (code "79") (name "ZX2") (class "Default")
      (node (ref "J5") (pin "P$4") (pinfunction "P$4_P$4") (pintype "bidirectional"))
      (node (ref "U3") (pin "24") (pinfunction "ZX2_24") (pintype "output"))
    )
    (net (code "80") (name "unconnected-(U3-NC-Pad46)") (class "Default")
      (node (ref "U3") (pin "46") (pinfunction "NC_46") (pintype "no_connect"))
    )
    (net (code "81") (name "unconnected-(U3-NC_2-Pad35)") (class "Default")
      (node (ref "U3") (pin "35") (pinfunction "NC_2_35") (pintype "no_connect"))
    )
    (net (code "82") (name "unconnected-(U3-NC_3-Pad45)") (class "Default")
      (node (ref "U3") (pin "45") (pinfunction "NC_3_45") (pintype "no_connect"))
    )
    (net (code "83") (name "unconnected-(U4-NC1-PadP$1)") (class "Default")
      (node (ref "U4") (pin "P$1") (pinfunction "NC1_P$1") (pintype "bidirectional"))
    )
    (net (code "84") (name "unconnected-(U4-NC2-PadP$4)") (class "Default")
      (node (ref "U4") (pin "P$4") (pinfunction "NC2_P$4") (pintype "bidirectional"))
    )
    (net (code "85") (name "unconnected-(U4-NC3-PadP$7)") (class "Default")
      (node (ref "U4") (pin "P$7") (pinfunction "NC3_P$7") (pintype "bidirectional"))
    )
  )
)
